# BIT_7.net
KiCad netlist of a schematic drawn in EasyEDA
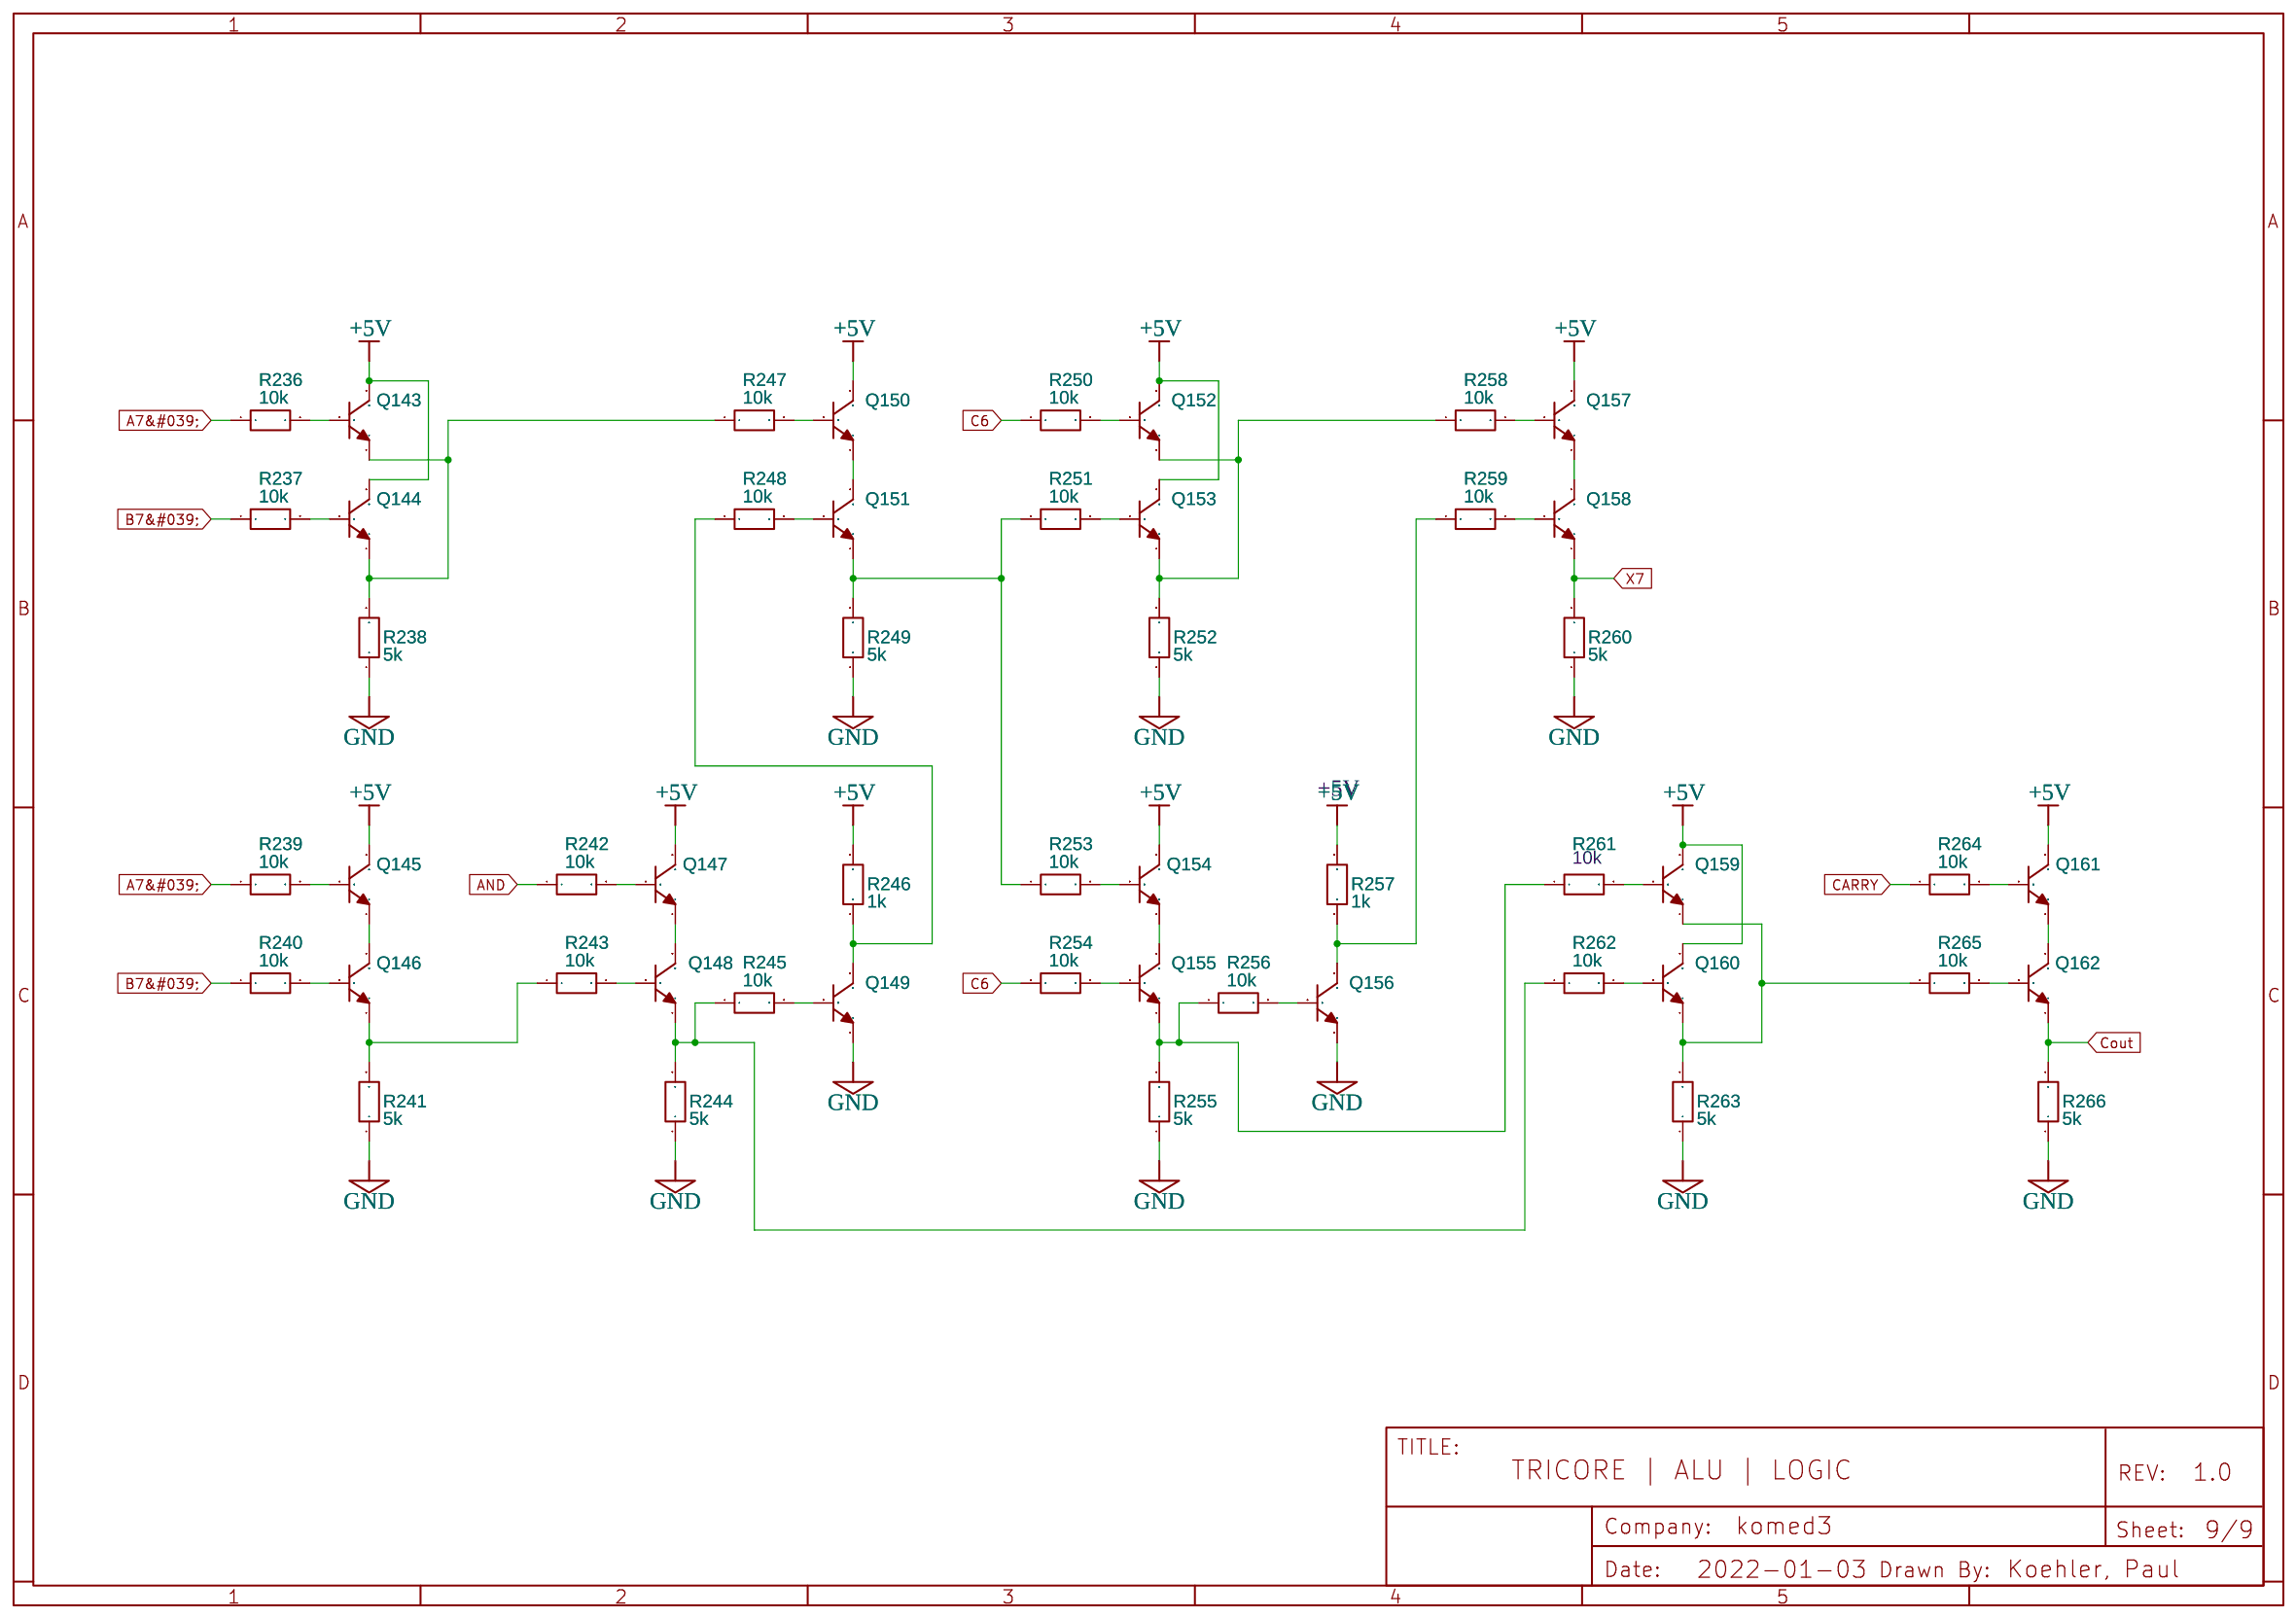
[diagram p0: schematic sheet]

(export (version "E")
  (design (tool "Eeschema 10.0.6"))
  (components
    (comp (ref "Q143")
      (value "2N3904(TO-92)")
      (fields (field (name "BOM_Manufacturer Part") "2N3904") (field (name "BOM_Supplier Part") "C118538"))
      (libsource (lib "") (part "2N3904(TO-92)"))
    )
    (comp (ref "Q144")
      (value "2N3904(TO-92)")
      (fields (field (name "BOM_Manufacturer Part") "2N3904") (field (name "BOM_Supplier Part") "C118538"))
      (libsource (lib "") (part "2N3904(TO-92)"))
    )
    (comp (ref "Q145")
      (value "2N3904(TO-92)")
      (fields (field (name "BOM_Manufacturer Part") "2N3904") (field (name "BOM_Supplier Part") "C118538"))
      (libsource (lib "") (part "2N3904(TO-92)"))
    )
    (comp (ref "Q146")
      (value "2N3904(TO-92)")
      (fields (field (name "BOM_Manufacturer Part") "2N3904") (field (name "BOM_Supplier Part") "C118538"))
      (libsource (lib "") (part "2N3904(TO-92)"))
    )
    (comp (ref "Q147")
      (value "2N3904(TO-92)")
      (fields (field (name "BOM_Manufacturer Part") "2N3904") (field (name "BOM_Supplier Part") "C118538"))
      (libsource (lib "") (part "2N3904(TO-92)"))
    )
    (comp (ref "Q148")
      (value "2N3904(TO-92)")
      (fields (field (name "BOM_Manufacturer Part") "2N3904") (field (name "BOM_Supplier Part") "C118538"))
      (libsource (lib "") (part "2N3904(TO-92)"))
    )
    (comp (ref "Q149")
      (value "2N3904(TO-92)")
      (fields (field (name "BOM_Manufacturer Part") "2N3904") (field (name "BOM_Supplier Part") "C118538"))
      (libsource (lib "") (part "2N3904(TO-92)"))
    )
    (comp (ref "Q150")
      (value "2N3904(TO-92)")
      (fields (field (name "BOM_Manufacturer Part") "2N3904") (field (name "BOM_Supplier Part") "C118538"))
      (libsource (lib "") (part "2N3904(TO-92)"))
    )
    (comp (ref "Q151")
      (value "2N3904(TO-92)")
      (fields (field (name "BOM_Manufacturer Part") "2N3904") (field (name "BOM_Supplier Part") "C118538"))
      (libsource (lib "") (part "2N3904(TO-92)"))
    )
    (comp (ref "Q152")
      (value "2N3904(TO-92)")
      (fields (field (name "BOM_Manufacturer Part") "2N3904") (field (name "BOM_Supplier Part") "C118538"))
      (libsource (lib "") (part "2N3904(TO-92)"))
    )
    (comp (ref "Q153")
      (value "2N3904(TO-92)")
      (fields (field (name "BOM_Manufacturer Part") "2N3904") (field (name "BOM_Supplier Part") "C118538"))
      (libsource (lib "") (part "2N3904(TO-92)"))
    )
    (comp (ref "Q154")
      (value "2N3904(TO-92)")
      (fields (field (name "BOM_Manufacturer Part") "2N3904") (field (name "BOM_Supplier Part") "C118538"))
      (libsource (lib "") (part "2N3904(TO-92)"))
    )
    (comp (ref "Q155")
      (value "2N3904(TO-92)")
      (fields (field (name "BOM_Manufacturer Part") "2N3904") (field (name "BOM_Supplier Part") "C118538"))
      (libsource (lib "") (part "2N3904(TO-92)"))
    )
    (comp (ref "Q156")
      (value "2N3904(TO-92)")
      (fields (field (name "BOM_Manufacturer Part") "2N3904") (field (name "BOM_Supplier Part") "C118538"))
      (libsource (lib "") (part "2N3904(TO-92)"))
    )
    (comp (ref "Q157")
      (value "2N3904(TO-92)")
      (fields (field (name "BOM_Manufacturer Part") "2N3904") (field (name "BOM_Supplier Part") "C118538"))
      (libsource (lib "") (part "2N3904(TO-92)"))
    )
    (comp (ref "Q158")
      (value "2N3904(TO-92)")
      (fields (field (name "BOM_Manufacturer Part") "2N3904") (field (name "BOM_Supplier Part") "C118538"))
      (libsource (lib "") (part "2N3904(TO-92)"))
    )
    (comp (ref "Q159")
      (value "2N3904(TO-92)")
      (fields (field (name "BOM_Manufacturer Part") "2N3904") (field (name "BOM_Supplier Part") "C118538"))
      (libsource (lib "") (part "2N3904(TO-92)"))
    )
    (comp (ref "Q160")
      (value "2N3904(TO-92)")
      (fields (field (name "BOM_Manufacturer Part") "2N3904") (field (name "BOM_Supplier Part") "C118538"))
      (libsource (lib "") (part "2N3904(TO-92)"))
    )
    (comp (ref "Q161")
      (value "2N3904(TO-92)")
      (fields (field (name "BOM_Manufacturer Part") "2N3904") (field (name "BOM_Supplier Part") "C118538"))
      (libsource (lib "") (part "2N3904(TO-92)"))
    )
    (comp (ref "Q162")
      (value "2N3904(TO-92)")
      (fields (field (name "BOM_Manufacturer Part") "2N3904") (field (name "BOM_Supplier Part") "C118538"))
      (libsource (lib "") (part "2N3904(TO-92)"))
    )
    (comp (ref "R236") (value "10k") (libsource (lib "") (part "R_AXIAL-0.3_EU")))
    (comp (ref "R237") (value "10k") (libsource (lib "") (part "R_AXIAL-0.3_EU")))
    (comp (ref "R238") (value "5k") (libsource (lib "") (part "R_AXIAL-0.3_EU_1")))
    (comp (ref "R239") (value "10k") (libsource (lib "") (part "R_AXIAL-0.3_EU")))
    (comp (ref "R240") (value "10k") (libsource (lib "") (part "R_AXIAL-0.3_EU")))
    (comp (ref "R241") (value "5k") (libsource (lib "") (part "R_AXIAL-0.3_EU_1")))
    (comp (ref "R242") (value "10k") (libsource (lib "") (part "R_AXIAL-0.3_EU")))
    (comp (ref "R243") (value "10k") (libsource (lib "") (part "R_AXIAL-0.3_EU")))
    (comp (ref "R244") (value "5k") (libsource (lib "") (part "R_AXIAL-0.3_EU_1")))
    (comp (ref "R245") (value "10k") (libsource (lib "") (part "R_AXIAL-0.3_EU")))
    (comp (ref "R246") (value "1k") (libsource (lib "") (part "R_AXIAL-0.3_EU_1")))
    (comp (ref "R247") (value "10k") (libsource (lib "") (part "R_AXIAL-0.3_EU")))
    (comp (ref "R248") (value "10k") (libsource (lib "") (part "R_AXIAL-0.3_EU")))
    (comp (ref "R249") (value "5k") (libsource (lib "") (part "R_AXIAL-0.3_EU_1")))
    (comp (ref "R250") (value "10k") (libsource (lib "") (part "R_AXIAL-0.3_EU")))
    (comp (ref "R251") (value "10k") (libsource (lib "") (part "R_AXIAL-0.3_EU")))
    (comp (ref "R252") (value "5k") (libsource (lib "") (part "R_AXIAL-0.3_EU_1")))
    (comp (ref "R253") (value "10k") (libsource (lib "") (part "R_AXIAL-0.3_EU")))
    (comp (ref "R254") (value "10k") (libsource (lib "") (part "R_AXIAL-0.3_EU")))
    (comp (ref "R255") (value "5k") (libsource (lib "") (part "R_AXIAL-0.3_EU_1")))
    (comp (ref "R256") (value "10k") (libsource (lib "") (part "R_AXIAL-0.3_EU")))
    (comp (ref "R257") (value "1k") (libsource (lib "") (part "R_AXIAL-0.3_EU_1")))
    (comp (ref "R258") (value "10k") (libsource (lib "") (part "R_AXIAL-0.3_EU")))
    (comp (ref "R259") (value "10k") (libsource (lib "") (part "R_AXIAL-0.3_EU")))
    (comp (ref "R260") (value "5k") (libsource (lib "") (part "R_AXIAL-0.3_EU_1")))
    (comp (ref "R261") (value "R224W") (libsource (lib "") (part "R_AXIAL-0.3_EU")))
    (comp (ref "R262") (value "10k") (libsource (lib "") (part "R_AXIAL-0.3_EU")))
    (comp (ref "R263") (value "5k") (libsource (lib "") (part "R_AXIAL-0.3_EU_1")))
    (comp (ref "R264") (value "10k") (libsource (lib "") (part "R_AXIAL-0.3_EU")))
    (comp (ref "R265") (value "10k") (libsource (lib "") (part "R_AXIAL-0.3_EU")))
    (comp (ref "R266") (value "5k") (libsource (lib "") (part "R_AXIAL-0.3_EU_1")))
  )
  (nets
    (net (code "1") (name "+5V") (class "Default")
      (node (ref "Q143") (pin "3") (pinfunction "C_3") (pintype "unspecified"))
      (node (ref "Q144") (pin "3") (pinfunction "C_3") (pintype "unspecified"))
      (node (ref "Q145") (pin "3") (pinfunction "C_3") (pintype "unspecified"))
      (node (ref "Q147") (pin "3") (pinfunction "C_3") (pintype "unspecified"))
      (node (ref "Q150") (pin "3") (pinfunction "C_3") (pintype "unspecified"))
      (node (ref "Q152") (pin "3") (pinfunction "C_3") (pintype "unspecified"))
      (node (ref "Q153") (pin "3") (pinfunction "C_3") (pintype "unspecified"))
      (node (ref "Q154") (pin "3") (pinfunction "C_3") (pintype "unspecified"))
      (node (ref "Q157") (pin "3") (pinfunction "C_3") (pintype "unspecified"))
      (node (ref "Q159") (pin "3") (pinfunction "C_3") (pintype "unspecified"))
      (node (ref "Q160") (pin "3") (pinfunction "C_3") (pintype "unspecified"))
      (node (ref "Q161") (pin "3") (pinfunction "C_3") (pintype "unspecified"))
      (node (ref "R246") (pin "2") (pinfunction "2_2") (pintype "unspecified"))
      (node (ref "R257") (pin "2") (pinfunction "2_2") (pintype "unspecified"))
    )
    (net (code "2") (name "A7&#039;") (class "Default")
      (node (ref "R236") (pin "1") (pinfunction "1_1") (pintype "unspecified"))
      (node (ref "R239") (pin "1") (pinfunction "1_1") (pintype "unspecified"))
    )
    (net (code "3") (name "AND") (class "Default")
      (node (ref "R242") (pin "1") (pinfunction "1_1") (pintype "unspecified"))
    )
    (net (code "4") (name "B7&#039;") (class "Default")
      (node (ref "R237") (pin "1") (pinfunction "1_1") (pintype "unspecified"))
      (node (ref "R240") (pin "1") (pinfunction "1_1") (pintype "unspecified"))
    )
    (net (code "5") (name "C6") (class "Default")
      (node (ref "R250") (pin "1") (pinfunction "1_1") (pintype "unspecified"))
      (node (ref "R254") (pin "1") (pinfunction "1_1") (pintype "unspecified"))
    )
    (net (code "6") (name "CARRY") (class "Default")
      (node (ref "R264") (pin "1") (pinfunction "1_1") (pintype "unspecified"))
    )
    (net (code "7") (name "Cout") (class "Default")
      (node (ref "Q162") (pin "1") (pinfunction "E_1") (pintype "unspecified"))
      (node (ref "R266") (pin "2") (pinfunction "2_2") (pintype "unspecified"))
    )
    (net (code "8") (name "GND") (class "Default")
      (node (ref "Q149") (pin "1") (pinfunction "E_1") (pintype "unspecified"))
      (node (ref "Q156") (pin "1") (pinfunction "E_1") (pintype "unspecified"))
      (node (ref "R238") (pin "1") (pinfunction "1_1") (pintype "unspecified"))
      (node (ref "R241") (pin "1") (pinfunction "1_1") (pintype "unspecified"))
      (node (ref "R244") (pin "1") (pinfunction "1_1") (pintype "unspecified"))
      (node (ref "R249") (pin "1") (pinfunction "1_1") (pintype "unspecified"))
      (node (ref "R252") (pin "1") (pinfunction "1_1") (pintype "unspecified"))
      (node (ref "R255") (pin "1") (pinfunction "1_1") (pintype "unspecified"))
      (node (ref "R260") (pin "1") (pinfunction "1_1") (pintype "unspecified"))
      (node (ref "R263") (pin "1") (pinfunction "1_1") (pintype "unspecified"))
      (node (ref "R266") (pin "1") (pinfunction "1_1") (pintype "unspecified"))
    )
    (net (code "9") (name "Net-(Q143-B)") (class "Default")
      (node (ref "Q143") (pin "2") (pinfunction "B_2") (pintype "unspecified"))
      (node (ref "R236") (pin "2") (pinfunction "2_2") (pintype "unspecified"))
    )
    (net (code "10") (name "Net-(Q143-E)") (class "Default")
      (node (ref "Q143") (pin "1") (pinfunction "E_1") (pintype "unspecified"))
      (node (ref "Q144") (pin "1") (pinfunction "E_1") (pintype "unspecified"))
      (node (ref "R238") (pin "2") (pinfunction "2_2") (pintype "unspecified"))
      (node (ref "R247") (pin "1") (pinfunction "1_1") (pintype "unspecified"))
    )
    (net (code "11") (name "Net-(Q144-B)") (class "Default")
      (node (ref "Q144") (pin "2") (pinfunction "B_2") (pintype "unspecified"))
      (node (ref "R237") (pin "2") (pinfunction "2_2") (pintype "unspecified"))
    )
    (net (code "12") (name "Net-(Q145-B)") (class "Default")
      (node (ref "Q145") (pin "2") (pinfunction "B_2") (pintype "unspecified"))
      (node (ref "R239") (pin "2") (pinfunction "2_2") (pintype "unspecified"))
    )
    (net (code "13") (name "Net-(Q145-E)") (class "Default")
      (node (ref "Q145") (pin "1") (pinfunction "E_1") (pintype "unspecified"))
      (node (ref "Q146") (pin "3") (pinfunction "C_3") (pintype "unspecified"))
    )
    (net (code "14") (name "Net-(Q146-B)") (class "Default")
      (node (ref "Q146") (pin "2") (pinfunction "B_2") (pintype "unspecified"))
      (node (ref "R240") (pin "2") (pinfunction "2_2") (pintype "unspecified"))
    )
    (net (code "15") (name "Net-(Q146-E)") (class "Default")
      (node (ref "Q146") (pin "1") (pinfunction "E_1") (pintype "unspecified"))
      (node (ref "R241") (pin "2") (pinfunction "2_2") (pintype "unspecified"))
      (node (ref "R243") (pin "1") (pinfunction "1_1") (pintype "unspecified"))
    )
    (net (code "16") (name "Net-(Q147-B)") (class "Default")
      (node (ref "Q147") (pin "2") (pinfunction "B_2") (pintype "unspecified"))
      (node (ref "R242") (pin "2") (pinfunction "2_2") (pintype "unspecified"))
    )
    (net (code "17") (name "Net-(Q147-E)") (class "Default")
      (node (ref "Q147") (pin "1") (pinfunction "E_1") (pintype "unspecified"))
      (node (ref "Q148") (pin "3") (pinfunction "C_3") (pintype "unspecified"))
    )
    (net (code "18") (name "Net-(Q148-B)") (class "Default")
      (node (ref "Q148") (pin "2") (pinfunction "B_2") (pintype "unspecified"))
      (node (ref "R243") (pin "2") (pinfunction "2_2") (pintype "unspecified"))
    )
    (net (code "19") (name "Net-(Q148-E)") (class "Default")
      (node (ref "Q148") (pin "1") (pinfunction "E_1") (pintype "unspecified"))
      (node (ref "R244") (pin "2") (pinfunction "2_2") (pintype "unspecified"))
      (node (ref "R245") (pin "1") (pinfunction "1_1") (pintype "unspecified"))
      (node (ref "R262") (pin "1") (pinfunction "1_1") (pintype "unspecified"))
    )
    (net (code "20") (name "Net-(Q149-B)") (class "Default")
      (node (ref "Q149") (pin "2") (pinfunction "B_2") (pintype "unspecified"))
      (node (ref "R245") (pin "2") (pinfunction "2_2") (pintype "unspecified"))
    )
    (net (code "21") (name "Net-(Q149-C)") (class "Default")
      (node (ref "Q149") (pin "3") (pinfunction "C_3") (pintype "unspecified"))
      (node (ref "R246") (pin "1") (pinfunction "1_1") (pintype "unspecified"))
      (node (ref "R248") (pin "1") (pinfunction "1_1") (pintype "unspecified"))
    )
    (net (code "22") (name "Net-(Q150-B)") (class "Default")
      (node (ref "Q150") (pin "2") (pinfunction "B_2") (pintype "unspecified"))
      (node (ref "R247") (pin "2") (pinfunction "2_2") (pintype "unspecified"))
    )
    (net (code "23") (name "Net-(Q150-E)") (class "Default")
      (node (ref "Q150") (pin "1") (pinfunction "E_1") (pintype "unspecified"))
      (node (ref "Q151") (pin "3") (pinfunction "C_3") (pintype "unspecified"))
    )
    (net (code "24") (name "Net-(Q151-B)") (class "Default")
      (node (ref "Q151") (pin "2") (pinfunction "B_2") (pintype "unspecified"))
      (node (ref "R248") (pin "2") (pinfunction "2_2") (pintype "unspecified"))
    )
    (net (code "25") (name "Net-(Q151-E)") (class "Default")
      (node (ref "Q151") (pin "1") (pinfunction "E_1") (pintype "unspecified"))
      (node (ref "R249") (pin "2") (pinfunction "2_2") (pintype "unspecified"))
      (node (ref "R251") (pin "1") (pinfunction "1_1") (pintype "unspecified"))
      (node (ref "R253") (pin "1") (pinfunction "1_1") (pintype "unspecified"))
    )
    (net (code "26") (name "Net-(Q152-B)") (class "Default")
      (node (ref "Q152") (pin "2") (pinfunction "B_2") (pintype "unspecified"))
      (node (ref "R250") (pin "2") (pinfunction "2_2") (pintype "unspecified"))
    )
    (net (code "27") (name "Net-(Q152-E)") (class "Default")
      (node (ref "Q152") (pin "1") (pinfunction "E_1") (pintype "unspecified"))
      (node (ref "Q153") (pin "1") (pinfunction "E_1") (pintype "unspecified"))
      (node (ref "R252") (pin "2") (pinfunction "2_2") (pintype "unspecified"))
      (node (ref "R258") (pin "1") (pinfunction "1_1") (pintype "unspecified"))
    )
    (net (code "28") (name "Net-(Q153-B)") (class "Default")
      (node (ref "Q153") (pin "2") (pinfunction "B_2") (pintype "unspecified"))
      (node (ref "R251") (pin "2") (pinfunction "2_2") (pintype "unspecified"))
    )
    (net (code "29") (name "Net-(Q154-B)") (class "Default")
      (node (ref "Q154") (pin "2") (pinfunction "B_2") (pintype "unspecified"))
      (node (ref "R253") (pin "2") (pinfunction "2_2") (pintype "unspecified"))
    )
    (net (code "30") (name "Net-(Q154-E)") (class "Default")
      (node (ref "Q154") (pin "1") (pinfunction "E_1") (pintype "unspecified"))
      (node (ref "Q155") (pin "3") (pinfunction "C_3") (pintype "unspecified"))
    )
    (net (code "31") (name "Net-(Q155-B)") (class "Default")
      (node (ref "Q155") (pin "2") (pinfunction "B_2") (pintype "unspecified"))
      (node (ref "R254") (pin "2") (pinfunction "2_2") (pintype "unspecified"))
    )
    (net (code "32") (name "Net-(Q155-E)") (class "Default")
      (node (ref "Q155") (pin "1") (pinfunction "E_1") (pintype "unspecified"))
      (node (ref "R255") (pin "2") (pinfunction "2_2") (pintype "unspecified"))
      (node (ref "R256") (pin "1") (pinfunction "1_1") (pintype "unspecified"))
      (node (ref "R261") (pin "1") (pinfunction "1_1") (pintype "unspecified"))
    )
    (net (code "33") (name "Net-(Q156-B)") (class "Default")
      (node (ref "Q156") (pin "2") (pinfunction "B_2") (pintype "unspecified"))
      (node (ref "R256") (pin "2") (pinfunction "2_2") (pintype "unspecified"))
    )
    (net (code "34") (name "Net-(Q156-C)") (class "Default")
      (node (ref "Q156") (pin "3") (pinfunction "C_3") (pintype "unspecified"))
      (node (ref "R257") (pin "1") (pinfunction "1_1") (pintype "unspecified"))
      (node (ref "R259") (pin "1") (pinfunction "1_1") (pintype "unspecified"))
    )
    (net (code "35") (name "Net-(Q157-B)") (class "Default")
      (node (ref "Q157") (pin "2") (pinfunction "B_2") (pintype "unspecified"))
      (node (ref "R258") (pin "2") (pinfunction "2_2") (pintype "unspecified"))
    )
    (net (code "36") (name "Net-(Q157-E)") (class "Default")
      (node (ref "Q157") (pin "1") (pinfunction "E_1") (pintype "unspecified"))
      (node (ref "Q158") (pin "3") (pinfunction "C_3") (pintype "unspecified"))
    )
    (net (code "37") (name "Net-(Q158-B)") (class "Default")
      (node (ref "Q158") (pin "2") (pinfunction "B_2") (pintype "unspecified"))
      (node (ref "R259") (pin "2") (pinfunction "2_2") (pintype "unspecified"))
    )
    (net (code "38") (name "Net-(Q159-B)") (class "Default")
      (node (ref "Q159") (pin "2") (pinfunction "B_2") (pintype "unspecified"))
      (node (ref "R261") (pin "2") (pinfunction "2_2") (pintype "unspecified"))
    )
    (net (code "39") (name "Net-(Q159-E)") (class "Default")
      (node (ref "Q159") (pin "1") (pinfunction "E_1") (pintype "unspecified"))
      (node (ref "Q160") (pin "1") (pinfunction "E_1") (pintype "unspecified"))
      (node (ref "R263") (pin "2") (pinfunction "2_2") (pintype "unspecified"))
      (node (ref "R265") (pin "1") (pinfunction "1_1") (pintype "unspecified"))
    )
    (net (code "40") (name "Net-(Q160-B)") (class "Default")
      (node (ref "Q160") (pin "2") (pinfunction "B_2") (pintype "unspecified"))
      (node (ref "R262") (pin "2") (pinfunction "2_2") (pintype "unspecified"))
    )
    (net (code "41") (name "Net-(Q161-B)") (class "Default")
      (node (ref "Q161") (pin "2") (pinfunction "B_2") (pintype "unspecified"))
      (node (ref "R264") (pin "2") (pinfunction "2_2") (pintype "unspecified"))
    )
    (net (code "42") (name "Net-(Q161-E)") (class "Default")
      (node (ref "Q161") (pin "1") (pinfunction "E_1") (pintype "unspecified"))
      (node (ref "Q162") (pin "3") (pinfunction "C_3") (pintype "unspecified"))
    )
    (net (code "43") (name "Net-(Q162-B)") (class "Default")
      (node (ref "Q162") (pin "2") (pinfunction "B_2") (pintype "unspecified"))
      (node (ref "R265") (pin "2") (pinfunction "2_2") (pintype "unspecified"))
    )
    (net (code "44") (name "X7") (class "Default")
      (node (ref "Q158") (pin "1") (pinfunction "E_1") (pintype "unspecified"))
      (node (ref "R260") (pin "2") (pinfunction "2_2") (pintype "unspecified"))
    )
  )
)
